# ETH-PHY.net
KiCad netlist of a schematic drawn in Altium Designer
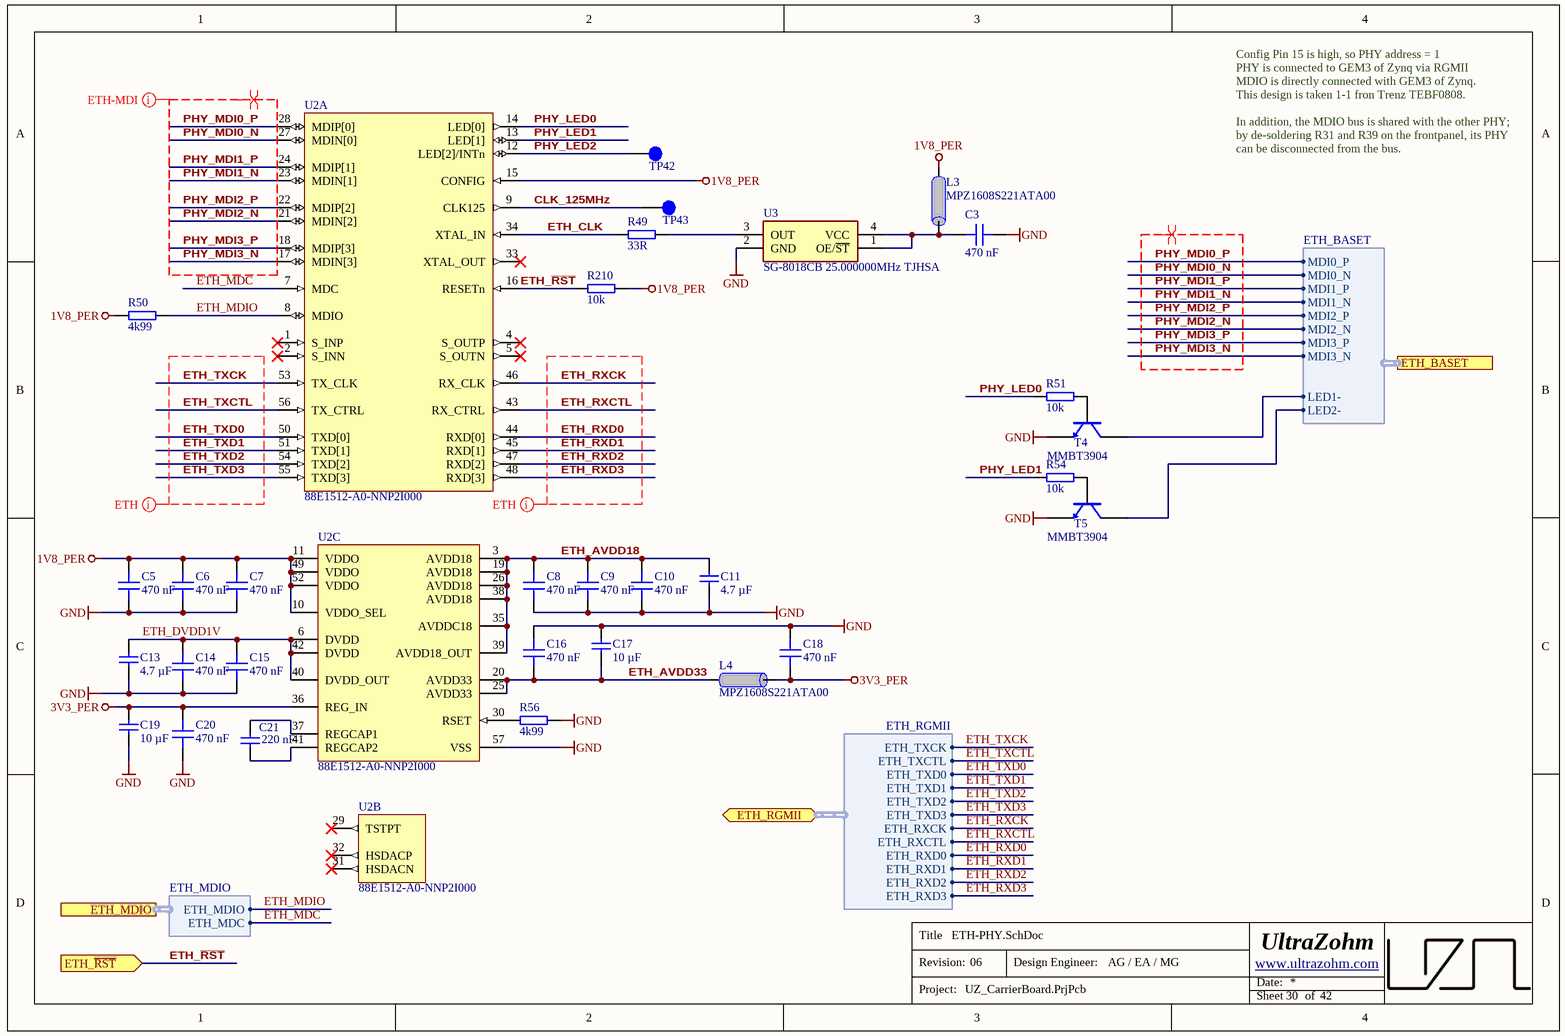
[diagram p0: ETH-PHY.SchDoc]

(export (version "E")
  (design (tool "Eeschema 10.0.6"))
  (components
    (comp (ref "C3")
      (value "470 nF")
      (footprint "C_0603_TE")
      (description "Capacitor 0603, 50 VDC, 470 nF, X5R")
      (fields
        (field (name "MANUFACTURER PART NUMBER") "CL10A474KB8NNNC")
        (field (name "MANUFACTURER") "Samsung Electro-Mechanics")
        (field (name "CREATED FROM") "AGeiger")
      )
      (libsource (lib "user") (part "Capacitor"))
    )
    (comp (ref "C5")
      (value "470 nF")
      (footprint "C_0603_TE")
      (description "Capacitor 0603, 50 VDC, 470 nF, X5R")
      (fields
        (field (name "MANUFACTURER PART NUMBER") "CL10A474KB8NNNC")
        (field (name "MANUFACTURER") "Samsung Electro-Mechanics")
        (field (name "CREATED FROM") "AGeiger")
      )
      (libsource (lib "user") (part "Capacitor"))
    )
    (comp (ref "C6")
      (value "470 nF")
      (footprint "C_0603_TE")
      (description "Capacitor 0603, 50 VDC, 470 nF, X5R")
      (fields
        (field (name "MANUFACTURER PART NUMBER") "CL10A474KB8NNNC")
        (field (name "MANUFACTURER") "Samsung Electro-Mechanics")
        (field (name "CREATED FROM") "AGeiger")
      )
      (libsource (lib "user") (part "Capacitor"))
    )
    (comp (ref "C7")
      (value "470 nF")
      (footprint "C_0603_TE")
      (description "Capacitor 0603, 50 VDC, 470 nF, X5R")
      (fields
        (field (name "MANUFACTURER PART NUMBER") "CL10A474KB8NNNC")
        (field (name "MANUFACTURER") "Samsung Electro-Mechanics")
        (field (name "CREATED FROM") "AGeiger")
      )
      (libsource (lib "user") (part "Capacitor"))
    )
    (comp (ref "C8")
      (value "470 nF")
      (footprint "C_0603_TE")
      (description "Capacitor 0603, 50 VDC, 470 nF, X5R")
      (fields
        (field (name "MANUFACTURER PART NUMBER") "CL10A474KB8NNNC")
        (field (name "MANUFACTURER") "Samsung Electro-Mechanics")
        (field (name "CREATED FROM") "AGeiger")
      )
      (libsource (lib "user") (part "Capacitor"))
    )
    (comp (ref "C9")
      (value "470 nF")
      (footprint "C_0603_TE")
      (description "Capacitor 0603, 50 VDC, 470 nF, X5R")
      (fields
        (field (name "MANUFACTURER PART NUMBER") "CL10A474KB8NNNC")
        (field (name "MANUFACTURER") "Samsung Electro-Mechanics")
        (field (name "CREATED FROM") "AGeiger")
      )
      (libsource (lib "user") (part "Capacitor"))
    )
    (comp (ref "C10")
      (value "470 nF")
      (footprint "C_0603_TE")
      (description "Capacitor 0603, 50 VDC, 470 nF, X5R")
      (fields
        (field (name "MANUFACTURER PART NUMBER") "CL10A474KB8NNNC")
        (field (name "MANUFACTURER") "Samsung Electro-Mechanics")
        (field (name "CREATED FROM") "AGeiger")
      )
      (libsource (lib "user") (part "Capacitor"))
    )
    (comp (ref "C11")
      (value "4.7 µF")
      (footprint "C_0603_TE")
      (description "Generic capacitor")
      (fields
        (field (name "TOLERANCE") "10 %")
        (field (name "MANUFACTURER PART NUMBER") "UZgen_C_0603_4.7uF_16V_X5R")
        (field (name "CREATED FROM") "MGeier")
      )
      (libsource (lib "user") (part "CAP-NP"))
    )
    (comp (ref "C13")
      (value "4.7 µF")
      (footprint "C_0603_TE")
      (description "Generic capacitor")
      (fields
        (field (name "TOLERANCE") "10 %")
        (field (name "MANUFACTURER PART NUMBER") "UZgen_C_0603_4.7uF_16V_X5R")
        (field (name "CREATED FROM") "MGeier")
      )
      (libsource (lib "user") (part "CAP-NP"))
    )
    (comp (ref "C14")
      (value "470 nF")
      (footprint "C_0603_TE")
      (description "Capacitor 0603, 50 VDC, 470 nF, X5R")
      (fields
        (field (name "MANUFACTURER PART NUMBER") "CL10A474KB8NNNC")
        (field (name "MANUFACTURER") "Samsung Electro-Mechanics")
        (field (name "CREATED FROM") "AGeiger")
      )
      (libsource (lib "user") (part "Capacitor"))
    )
    (comp (ref "C15")
      (value "470 nF")
      (footprint "C_0603_TE")
      (description "Capacitor 0603, 50 VDC, 470 nF, X5R")
      (fields
        (field (name "MANUFACTURER PART NUMBER") "CL10A474KB8NNNC")
        (field (name "MANUFACTURER") "Samsung Electro-Mechanics")
        (field (name "CREATED FROM") "AGeiger")
      )
      (libsource (lib "user") (part "Capacitor"))
    )
    (comp (ref "C16")
      (value "470 nF")
      (footprint "C_0603_TE")
      (description "Capacitor 0603, 50 VDC, 470 nF, X5R")
      (fields
        (field (name "MANUFACTURER PART NUMBER") "CL10A474KB8NNNC")
        (field (name "MANUFACTURER") "Samsung Electro-Mechanics")
        (field (name "CREATED FROM") "AGeiger")
      )
      (libsource (lib "user") (part "Capacitor"))
    )
    (comp (ref "C17")
      (value "10 µF")
      (footprint "C_0603_TE")
      (description "Generic capacitor")
      (fields
        (field (name "MANUFACTURER PART NUMBER") "UZgen_C_0603_10uF_6.3V_X7R")
        (field (name "MANUFACTURER") "UZgen")
        (field (name "CREATED FROM") "UZgenTool")
      )
      (libsource (lib "user") (part "CAP-NP"))
    )
    (comp (ref "C18")
      (value "470 nF")
      (footprint "C_0603_TE")
      (description "Capacitor 0603, 50 VDC, 470 nF, X5R")
      (fields
        (field (name "MANUFACTURER PART NUMBER") "CL10A474KB8NNNC")
        (field (name "MANUFACTURER") "Samsung Electro-Mechanics")
        (field (name "CREATED FROM") "AGeiger")
      )
      (libsource (lib "user") (part "Capacitor"))
    )
    (comp (ref "C19")
      (value "10 µF")
      (footprint "C_0603_TE")
      (description "Generic capacitor")
      (fields
        (field (name "MANUFACTURER PART NUMBER") "UZgen_C_0603_10uF_6.3V_X7R")
        (field (name "MANUFACTURER") "UZgen")
        (field (name "CREATED FROM") "UZgenTool")
      )
      (libsource (lib "user") (part "CAP-NP"))
    )
    (comp (ref "C20")
      (value "470 nF")
      (footprint "C_0603_TE")
      (description "Capacitor 0603, 50 VDC, 470 nF, X5R")
      (fields
        (field (name "MANUFACTURER PART NUMBER") "CL10A474KB8NNNC")
        (field (name "MANUFACTURER") "Samsung Electro-Mechanics")
        (field (name "CREATED FROM") "AGeiger")
      )
      (libsource (lib "user") (part "Capacitor"))
    )
    (comp (ref "C21")
      (value "220 nF")
      (footprint "C_0603_TE")
      (description "Generic capacitor")
      (fields
        (field (name "TOLERANCE") "10 %")
        (field (name "VOLTAGE") "50V")
        (field (name "CREATED FROM") "UZgenTool")
      )
      (libsource (lib "user") (part "CAP-NP"))
    )
    (comp (ref "L3")
      (value "MPZ1608S221ATA00")
      (footprint "RES 0603_1608")
      (description "Ferritperle, 0603, 220 ohm, 2.2 A, Baureihe MPZ, 0.05 ohm, ± 25%")
      (fields
        (field (name "MANUFACTURER") "TDK")
        (field (name "LCSC PART NUMBER") "C76815")
        (field (name "CREATED FROM") "MGremer")
      )
      (libsource (lib "user") (part "Ferrite_Bead"))
    )
    (comp (ref "L4")
      (value "MPZ1608S221ATA00")
      (footprint "RES 0603_1608")
      (description "Ferritperle, 0603, 220 ohm, 2.2 A, Baureihe MPZ, 0.05 ohm, ± 25%")
      (fields
        (field (name "MANUFACTURER") "TDK")
        (field (name "LCSC PART NUMBER") "C76815")
        (field (name "CREATED FROM") "MGremer")
      )
      (libsource (lib "") (part "Ferrite_Bead_1"))
    )
    (comp (ref "R49")
      (value "33R")
      (footprint "R_0603_TE")
      (description "Generic resistor")
      (fields
        (field (name "TOLERANCE") "1 %")
        (field (name "MANUFACTURER PART NUMBER") "UZgen_R_0603_33R")
        (field (name "CREATED FROM") "UZgenTool")
      )
      (libsource (lib "user") (part "RES"))
    )
    (comp (ref "R50")
      (value "4k99")
      (footprint "RES 0603_1608")
      (fields
        (field (name "TOLERANCE") "1%")
        (field (name "MANUFACTURER PART NUMBER") "0603WAF4991T5E")
        (field (name "MANUFACTURER") "UNI-ROYAL(Uniroyal Elec)")
        (field (name "CREATED FROM") "NDiringer")
      )
      (libsource (lib "user") (part "Resistor"))
    )
    (comp (ref "R51")
      (value "10k")
      (footprint "R_0603_TE")
      (description "Generic resistor")
      (fields
        (field (name "TOLERANCE") "1 %")
        (field (name "MANUFACTURER PART NUMBER") "UZgen_R_0603_10k")
        (field (name "CREATED FROM") "AGeiger")
      )
      (libsource (lib "user") (part "RES"))
    )
    (comp (ref "R54")
      (value "10k")
      (footprint "R_0603_TE")
      (description "Generic resistor")
      (fields
        (field (name "TOLERANCE") "1 %")
        (field (name "MANUFACTURER PART NUMBER") "UZgen_R_0603_10k")
        (field (name "CREATED FROM") "AGeiger")
      )
      (libsource (lib "user") (part "RES"))
    )
    (comp (ref "R56")
      (value "4k99")
      (footprint "RES 0603_1608")
      (fields
        (field (name "TOLERANCE") "1%")
        (field (name "MANUFACTURER PART NUMBER") "0603WAF4991T5E")
        (field (name "MANUFACTURER") "UNI-ROYAL(Uniroyal Elec)")
        (field (name "CREATED FROM") "NDiringer")
      )
      (libsource (lib "user") (part "Resistor"))
    )
    (comp (ref "R210")
      (value "10k")
      (footprint "R_0603_TE")
      (description "Generic resistor")
      (fields
        (field (name "TOLERANCE") "1 %")
        (field (name "MANUFACTURER PART NUMBER") "UZgen_R_0603_10k")
        (field (name "CREATED FROM") "AGeiger")
      )
      (libsource (lib "user") (part "RES"))
    )
    (comp (ref "T4")
      (value "MMBT3904")
      (footprint "SOT95P280X145-3N")
      (fields
        (field (name "MANUFACTURER") "Jiangsu Changjing Electronics Technology Co., Ltd.")
        (field (name "LCSC PART NUMBER") "C20526")
        (field (name "CREATED FROM") "NDiringer")
      )
      (libsource (lib "user") (part "NPN-SOT23"))
    )
    (comp (ref "T5")
      (value "MMBT3904")
      (footprint "SOT95P280X145-3N")
      (fields
        (field (name "MANUFACTURER") "Jiangsu Changjing Electronics Technology Co., Ltd.")
        (field (name "LCSC PART NUMBER") "C20526")
        (field (name "CREATED FROM") "NDiringer")
      )
      (libsource (lib "user") (part "NPN-SOT23"))
    )
    (comp (ref "TP42")
      (value "Testpoint 1mm")
      (footprint "TP_1mm")
      (fields
        (field (name "MANUFACTURER PART NUMBER") "NULL")
        (field (name "CREATED") "2018_06_25_AGeiger")
        (field (name "CREATED FROM") "AGeiger")
      )
      (libsource (lib "user") (part "TP_1mm"))
    )
    (comp (ref "TP43")
      (value "Testpoint 1mm")
      (footprint "TP_1mm")
      (fields
        (field (name "MANUFACTURER PART NUMBER") "NULL")
        (field (name "CREATED") "2018_06_25_AGeiger")
        (field (name "CREATED FROM") "AGeiger")
      )
      (libsource (lib "user") (part "TP_1mm"))
    )
    (comp (ref "U2")
      (value "88E1512-A0-NNP2I000")
      (footprint "QFN50P800X800X100-57N")
      (description "Ethernet ICs Single-Port EEE GE PHY w/SGMII in 56-pin QFN")
      (fields
        (field (name "MANUFACTURER") "Marvell")
        (field (name "LCSC PART NUMBER") "C713256")
        (field (name "CREATED FROM") "MGremer")
      )
      (libsource (lib "user") (part "88E1512"))
    )
    (comp (ref "U3")
      (value "SG-8018CB 25.000000MHz TJHSA")
      (footprint "SMD5032-4P")
      (description "±50ppm 1.8V~3.3V 25MHz SMD5032-4P Programmable Oscillators ROHS")
      (fields
        (field (name "MANUFACTURER") "Seiko Epson")
        (field (name "LCSC PART NUMBER") "C390471")
        (field (name "CREATED FROM") "FRosner")
      )
      (libsource (lib "user") (part "SG-8018CB"))
    )
  )
  (nets
    (net (code "3") (name "/CLK_125MHz") (class "Default")
      (node (ref "TP43") (pin "1") (pintype "passive"))
      (node (ref "U2") (pin "9") (pinfunction "CLK125_9") (pintype "output"))
    )
    (net (code "4") (name "/ETH_AVDD18") (class "Default")
      (node (ref "C10") (pin "1") (pinfunction "1_1") (pintype "passive"))
      (node (ref "C11") (pin "1") (pinfunction "1_1") (pintype "passive"))
      (node (ref "C8") (pin "1") (pinfunction "1_1") (pintype "passive"))
      (node (ref "C9") (pin "1") (pinfunction "1_1") (pintype "passive"))
      (node (ref "U2") (pin "19") (pinfunction "AVDD18_19") (pintype "power_in"))
      (node (ref "U2") (pin "26") (pinfunction "AVDD18_26") (pintype "power_in"))
      (node (ref "U2") (pin "3") (pinfunction "AVDD18_3") (pintype "power_in"))
      (node (ref "U2") (pin "35") (pinfunction "AVDDC18_35") (pintype "power_in"))
      (node (ref "U2") (pin "38") (pinfunction "AVDD18_38") (pintype "power_in"))
      (node (ref "U2") (pin "39") (pinfunction "AVDD18_OUT_39") (pintype "power_in"))
    )
    (net (code "5") (name "/ETH_AVDD33") (class "Default")
      (node (ref "C16") (pin "2") (pinfunction "2_2") (pintype "passive"))
      (node (ref "C17") (pin "2") (pinfunction "2_2") (pintype "passive"))
      (node (ref "L4") (pin "1") (pinfunction "1_1") (pintype "passive"))
      (node (ref "U2") (pin "20") (pinfunction "AVDD33_20") (pintype "power_in"))
      (node (ref "U2") (pin "25") (pinfunction "AVDD33_25") (pintype "power_in"))
    )
    (net (code "6") (name "/ETH_CLK") (class "Default")
      (node (ref "R49") (pin "1") (pinfunction "1_1") (pintype "passive"))
      (node (ref "U2") (pin "34") (pinfunction "XTAL_IN_34") (pintype "input"))
    )
    (net (code "7") (name "/ETH_DVDD1V") (class "Default")
      (node (ref "C13") (pin "1") (pinfunction "1_1") (pintype "passive"))
      (node (ref "C14") (pin "1") (pinfunction "1_1") (pintype "passive"))
      (node (ref "C15") (pin "1") (pinfunction "1_1") (pintype "passive"))
      (node (ref "U2") (pin "40") (pinfunction "DVDD_OUT_40") (pintype "power_in"))
      (node (ref "U2") (pin "42") (pinfunction "DVDD_42") (pintype "power_in"))
      (node (ref "U2") (pin "6") (pinfunction "DVDD_6") (pintype "power_in"))
    )
    (net (code "8") (name "/ETH_MDC") (class "Default")
      (node (ref "U2") (pin "7") (pinfunction "MDC_7") (pintype "input"))
    )
    (net (code "9") (name "/ETH_MDIO") (class "Default")
      (node (ref "R50") (pin "2") (pinfunction "2_2") (pintype "passive"))
      (node (ref "U2") (pin "8") (pinfunction "MDIO_8") (pintype "bidirectional"))
    )
    (net (code "10") (name "/ETH_RXCK") (class "Default")
      (node (ref "U2") (pin "46") (pinfunction "RX_CLK_46") (pintype "output"))
    )
    (net (code "11") (name "/ETH_RXCTL") (class "Default")
      (node (ref "U2") (pin "43") (pinfunction "RX_CTRL_43") (pintype "output"))
    )
    (net (code "12") (name "/ETH_RXD0") (class "Default")
      (node (ref "U2") (pin "44") (pinfunction "RXD[0]_44") (pintype "output"))
    )
    (net (code "13") (name "/ETH_RXD1") (class "Default")
      (node (ref "U2") (pin "45") (pinfunction "RXD[1]_45") (pintype "output"))
    )
    (net (code "14") (name "/ETH_RXD2") (class "Default")
      (node (ref "U2") (pin "47") (pinfunction "RXD[2]_47") (pintype "output"))
    )
    (net (code "15") (name "/ETH_RXD3") (class "Default")
      (node (ref "U2") (pin "48") (pinfunction "RXD[3]_48") (pintype "output"))
    )
    (net (code "16") (name "/ETH_TXCK") (class "Default")
      (node (ref "U2") (pin "53") (pinfunction "TX_CLK_53") (pintype "input"))
    )
    (net (code "17") (name "/ETH_TXCTL") (class "Default")
      (node (ref "U2") (pin "56") (pinfunction "TX_CTRL_56") (pintype "input"))
    )
    (net (code "18") (name "/ETH_TXD0") (class "Default")
      (node (ref "U2") (pin "50") (pinfunction "TXD[0]_50") (pintype "input"))
    )
    (net (code "19") (name "/ETH_TXD1") (class "Default")
      (node (ref "U2") (pin "51") (pinfunction "TXD[1]_51") (pintype "input"))
    )
    (net (code "20") (name "/ETH_TXD2") (class "Default")
      (node (ref "U2") (pin "54") (pinfunction "TXD[2]_54") (pintype "input"))
    )
    (net (code "21") (name "/ETH_TXD3") (class "Default")
      (node (ref "U2") (pin "55") (pinfunction "TXD[3]_55") (pintype "input"))
    )
    (net (code "22") (name "/ETH_~{RST}") (class "Default")
      (node (ref "R210") (pin "1") (pinfunction "1_1") (pintype "passive"))
      (node (ref "U2") (pin "16") (pinfunction "RESETn_16") (pintype "input"))
    )
    (net (code "23") (name "/LED1-") (class "Default")
      (node (ref "T4") (pin "3") (pinfunction "COLLECTOR_3") (pintype "passive"))
    )
    (net (code "24") (name "/LED2-") (class "Default")
      (node (ref "T5") (pin "3") (pinfunction "COLLECTOR_3") (pintype "passive"))
    )
    (net (code "25") (name "/PHY_LED0") (class "Default")
      (node (ref "R51") (pin "1") (pinfunction "1_1") (pintype "passive"))
      (node (ref "U2") (pin "14") (pinfunction "LED[0]_14") (pintype "output"))
    )
    (net (code "26") (name "/PHY_LED1") (class "Default")
      (node (ref "R54") (pin "1") (pinfunction "1_1") (pintype "passive"))
      (node (ref "U2") (pin "13") (pinfunction "LED[1]_13") (pintype "bidirectional"))
    )
    (net (code "27") (name "/PHY_LED2") (class "Default")
      (node (ref "TP42") (pin "1") (pintype "passive"))
      (node (ref "U2") (pin "12") (pinfunction "LED[2]/INTn_12") (pintype "bidirectional"))
    )
    (net (code "28") (name "/PHY_MDI0_N") (class "Default")
      (node (ref "U2") (pin "27") (pinfunction "MDIN[0]_27") (pintype "bidirectional"))
    )
    (net (code "29") (name "/PHY_MDI0_P") (class "Default")
      (node (ref "U2") (pin "28") (pinfunction "MDIP[0]_28") (pintype "bidirectional"))
    )
    (net (code "30") (name "/PHY_MDI1_N") (class "Default")
      (node (ref "U2") (pin "23") (pinfunction "MDIN[1]_23") (pintype "bidirectional"))
    )
    (net (code "31") (name "/PHY_MDI1_P") (class "Default")
      (node (ref "U2") (pin "24") (pinfunction "MDIP[1]_24") (pintype "bidirectional"))
    )
    (net (code "32") (name "/PHY_MDI2_N") (class "Default")
      (node (ref "U2") (pin "21") (pinfunction "MDIN[2]_21") (pintype "bidirectional"))
    )
    (net (code "33") (name "/PHY_MDI2_P") (class "Default")
      (node (ref "U2") (pin "22") (pinfunction "MDIP[2]_22") (pintype "bidirectional"))
    )
    (net (code "34") (name "/PHY_MDI3_N") (class "Default")
      (node (ref "U2") (pin "17") (pinfunction "MDIN[3]_17") (pintype "bidirectional"))
    )
    (net (code "35") (name "/PHY_MDI3_P") (class "Default")
      (node (ref "U2") (pin "18") (pinfunction "MDIP[3]_18") (pintype "bidirectional"))
    )
    (net (code "39") (name "1V8_PER") (class "Default")
      (node (ref "C5") (pin "1") (pinfunction "1_1") (pintype "passive"))
      (node (ref "C6") (pin "1") (pinfunction "1_1") (pintype "passive"))
      (node (ref "C7") (pin "1") (pinfunction "1_1") (pintype "passive"))
      (node (ref "L3") (pin "1") (pinfunction "1_1") (pintype "passive"))
      (node (ref "R210") (pin "2") (pinfunction "2_2") (pintype "passive"))
      (node (ref "R50") (pin "1") (pinfunction "1_1") (pintype "passive"))
      (node (ref "U2") (pin "10") (pinfunction "VDDO_SEL_10") (pintype "power_in"))
      (node (ref "U2") (pin "11") (pinfunction "VDDO_11") (pintype "power_in"))
      (node (ref "U2") (pin "15") (pinfunction "CONFIG_15") (pintype "input"))
      (node (ref "U2") (pin "49") (pinfunction "VDDO_49") (pintype "power_in"))
      (node (ref "U2") (pin "52") (pinfunction "VDDO_52") (pintype "power_in"))
    )
    (net (code "40") (name "3V3_PER") (class "Default")
      (node (ref "C18") (pin "2") (pinfunction "2_2") (pintype "passive"))
      (node (ref "C19") (pin "1") (pinfunction "1_1") (pintype "passive"))
      (node (ref "C20") (pin "1") (pinfunction "1_1") (pintype "passive"))
      (node (ref "L4") (pin "2") (pinfunction "2_2") (pintype "passive"))
      (node (ref "U2") (pin "36") (pinfunction "REG_IN_36") (pintype "power_in"))
    )
    (net (code "41") (name "GND") (class "Default")
      (node (ref "C10") (pin "2") (pinfunction "2_2") (pintype "passive"))
      (node (ref "C11") (pin "2") (pinfunction "2_2") (pintype "passive"))
      (node (ref "C13") (pin "2") (pinfunction "2_2") (pintype "passive"))
      (node (ref "C14") (pin "2") (pinfunction "2_2") (pintype "passive"))
      (node (ref "C15") (pin "2") (pinfunction "2_2") (pintype "passive"))
      (node (ref "C16") (pin "1") (pinfunction "1_1") (pintype "passive"))
      (node (ref "C17") (pin "1") (pinfunction "1_1") (pintype "passive"))
      (node (ref "C18") (pin "1") (pinfunction "1_1") (pintype "passive"))
      (node (ref "C19") (pin "2") (pinfunction "2_2") (pintype "passive"))
      (node (ref "C20") (pin "2") (pinfunction "2_2") (pintype "passive"))
      (node (ref "C3") (pin "1") (pinfunction "1_1") (pintype "passive"))
      (node (ref "C5") (pin "2") (pinfunction "2_2") (pintype "passive"))
      (node (ref "C6") (pin "2") (pinfunction "2_2") (pintype "passive"))
      (node (ref "C7") (pin "2") (pinfunction "2_2") (pintype "passive"))
      (node (ref "C8") (pin "2") (pinfunction "2_2") (pintype "passive"))
      (node (ref "C9") (pin "2") (pinfunction "2_2") (pintype "passive"))
      (node (ref "R56") (pin "2") (pinfunction "2_2") (pintype "passive"))
      (node (ref "T4") (pin "2") (pinfunction "EMITTER_2") (pintype "passive"))
      (node (ref "T5") (pin "2") (pinfunction "EMITTER_2") (pintype "passive"))
      (node (ref "U2") (pin "57") (pinfunction "VSS_57") (pintype "power_in"))
      (node (ref "U3") (pin "2") (pinfunction "GND_2") (pintype "passive"))
    )
    (net (code "42") (name "Net-(T4-BASIS)") (class "Default")
      (node (ref "R51") (pin "2") (pinfunction "2_2") (pintype "passive"))
      (node (ref "T4") (pin "1") (pinfunction "BASIS_1") (pintype "passive"))
    )
    (net (code "43") (name "Net-(T5-BASIS)") (class "Default")
      (node (ref "R54") (pin "2") (pinfunction "2_2") (pintype "passive"))
      (node (ref "T5") (pin "1") (pinfunction "BASIS_1") (pintype "passive"))
    )
    (net (code "44") (name "Net-(U2C-REGCAP1)") (class "Default")
      (node (ref "C21") (pin "1") (pinfunction "1_1") (pintype "passive"))
      (node (ref "U2") (pin "37") (pinfunction "REGCAP1_37") (pintype "passive"))
    )
    (net (code "45") (name "Net-(U2C-REGCAP2)") (class "Default")
      (node (ref "C21") (pin "2") (pinfunction "2_2") (pintype "passive"))
      (node (ref "U2") (pin "41") (pinfunction "REGCAP2_41") (pintype "passive"))
    )
    (net (code "46") (name "Net-(U2C-RSET)") (class "Default")
      (node (ref "R56") (pin "1") (pinfunction "1_1") (pintype "passive"))
      (node (ref "U2") (pin "30") (pinfunction "RSET_30") (pintype "input"))
    )
    (net (code "47") (name "Net-(U3-OE{slash}~{ST})") (class "Default")
      (node (ref "C3") (pin "2") (pinfunction "2_2") (pintype "passive"))
      (node (ref "L3") (pin "2") (pinfunction "2_2") (pintype "passive"))
      (node (ref "U3") (pin "1") (pinfunction "OE/~{ST}_1") (pintype "passive"))
      (node (ref "U3") (pin "4") (pinfunction "VCC_4") (pintype "passive"))
    )
    (net (code "48") (name "Net-(U3-OUT)") (class "Default")
      (node (ref "R49") (pin "2") (pinfunction "2_2") (pintype "passive"))
      (node (ref "U3") (pin "3") (pinfunction "OUT_3") (pintype "passive"))
    )
    (net (code "49") (name "unconnected-(U2A-S_INN-Pad2)") (class "Default")
      (node (ref "U2") (pin "2") (pinfunction "S_INN_2") (pintype "input+no_connect"))
    )
    (net (code "50") (name "unconnected-(U2A-S_INP-Pad1)") (class "Default")
      (node (ref "U2") (pin "1") (pinfunction "S_INP_1") (pintype "input+no_connect"))
    )
    (net (code "51") (name "unconnected-(U2A-S_OUTN-Pad5)") (class "Default")
      (node (ref "U2") (pin "5") (pinfunction "S_OUTN_5") (pintype "output+no_connect"))
    )
    (net (code "52") (name "unconnected-(U2A-S_OUTP-Pad4)") (class "Default")
      (node (ref "U2") (pin "4") (pinfunction "S_OUTP_4") (pintype "output+no_connect"))
    )
    (net (code "53") (name "unconnected-(U2A-XTAL_OUT-Pad33)") (class "Default")
      (node (ref "U2") (pin "33") (pinfunction "XTAL_OUT_33") (pintype "output+no_connect"))
    )
    (net (code "54") (name "unconnected-(U2B-HSDACN-Pad31)") (class "Default")
      (node (ref "U2") (pin "31") (pinfunction "HSDACN_31") (pintype "output+no_connect"))
    )
    (net (code "55") (name "unconnected-(U2B-HSDACP-Pad32)") (class "Default")
      (node (ref "U2") (pin "32") (pinfunction "HSDACP_32") (pintype "output+no_connect"))
    )
    (net (code "56") (name "unconnected-(U2B-TSTPT-Pad29)") (class "Default")
      (node (ref "U2") (pin "29") (pinfunction "TSTPT_29") (pintype "output+no_connect"))
    )
  )
)
